# ads1115_2.net
KiCad netlist of a schematic drawn in EAGLE
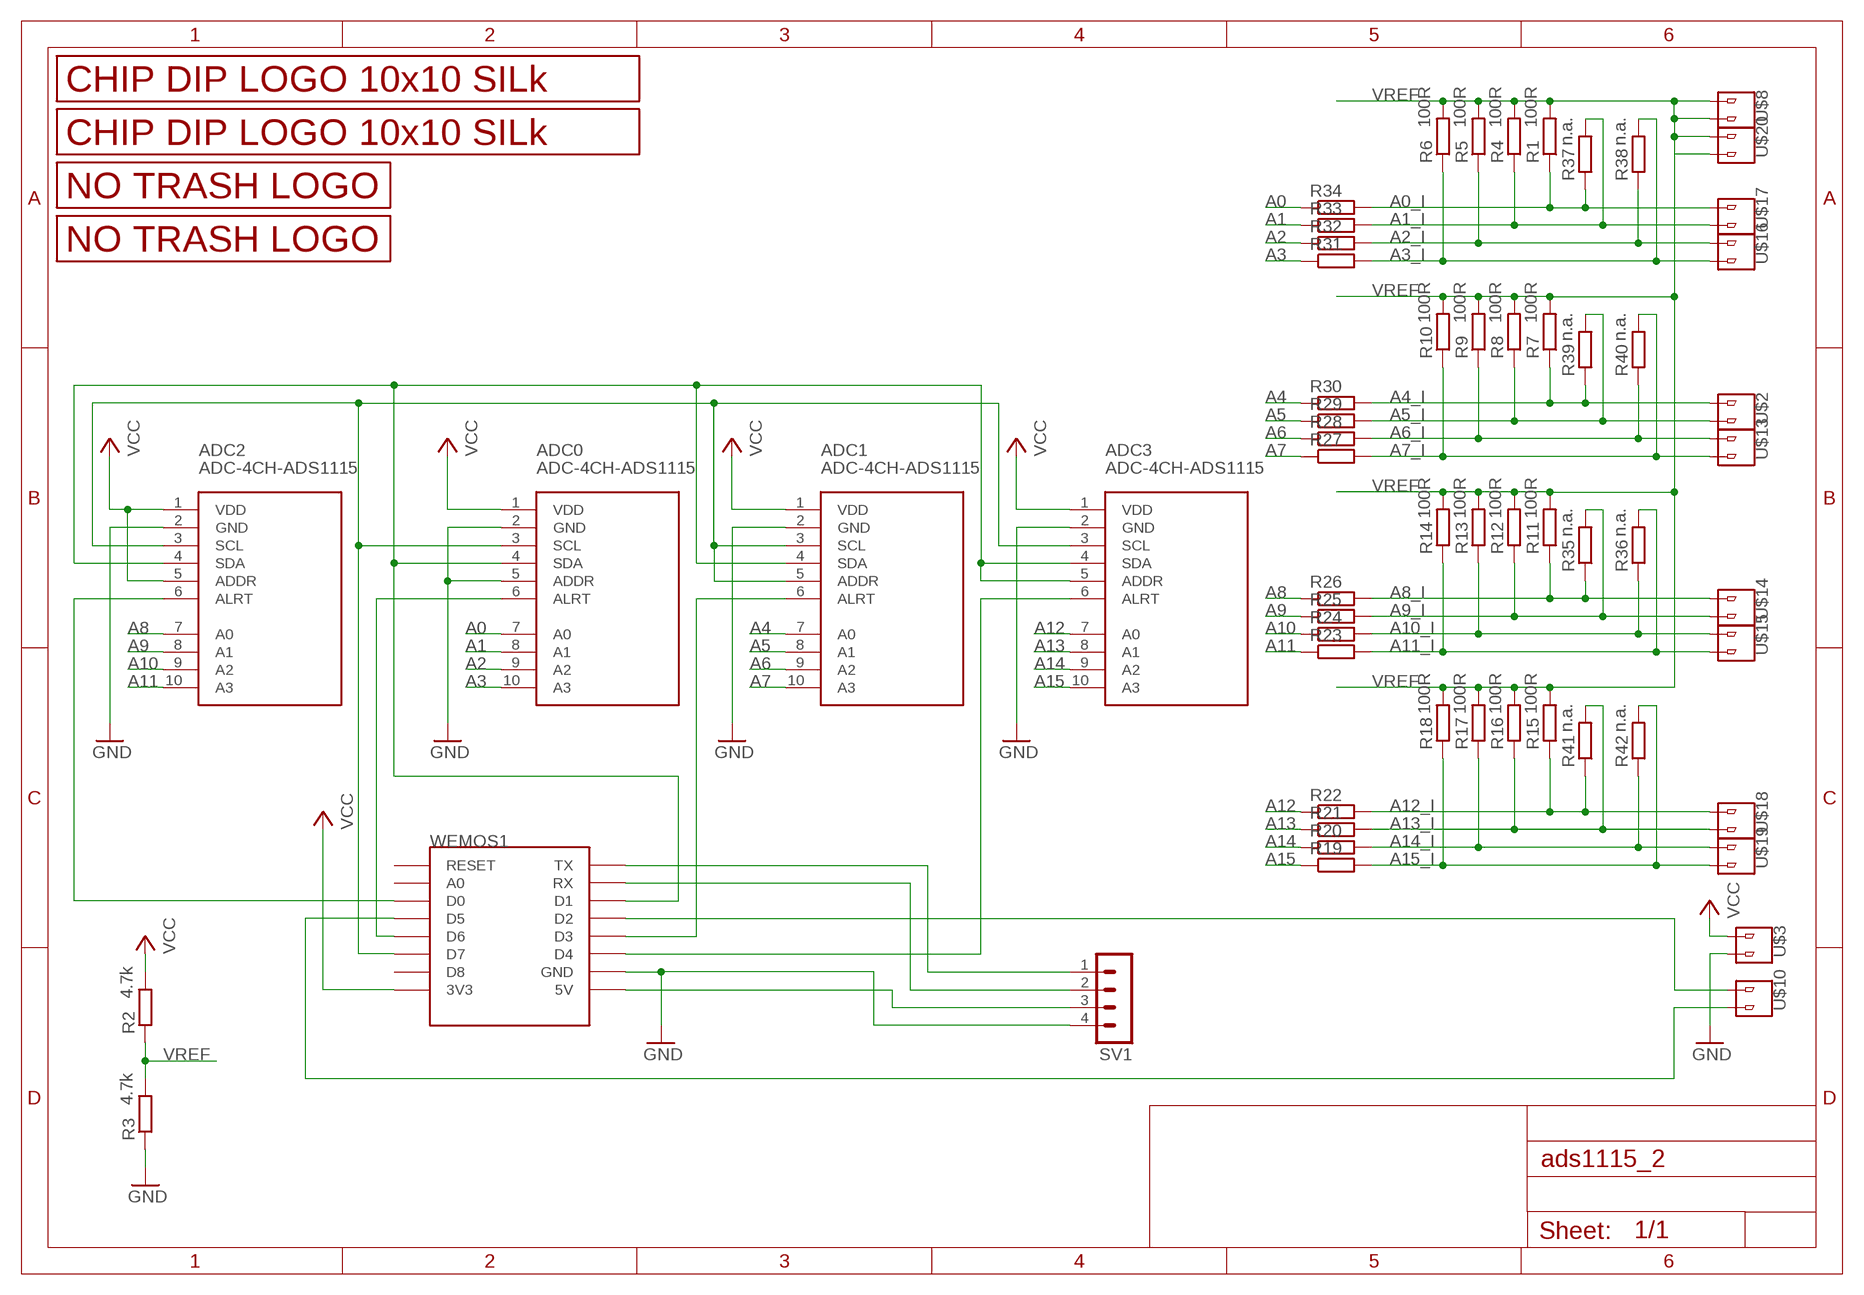
[diagram p0: schematic, sheet 1]

(export (version "E")
  (design (tool "Eeschema 10.0.6"))
  (components
    (comp (ref "ADC0")
      (value "ADC-4CH-ADS1115")
      (footprint "eagle-import:ADC-4CH-ADS1115_NO")
      (libsource (lib "eagle-import") (part "ADC-4CH-ADS1115"))
    )
    (comp (ref "ADC1")
      (value "ADC-4CH-ADS1115")
      (footprint "eagle-import:ADC-4CH-ADS1115_NO")
      (libsource (lib "eagle-import") (part "ADC-4CH-ADS1115"))
    )
    (comp (ref "ADC2")
      (value "ADC-4CH-ADS1115")
      (footprint "eagle-import:ADC-4CH-ADS1115_NO")
      (libsource (lib "eagle-import") (part "ADC-4CH-ADS1115"))
    )
    (comp (ref "ADC3")
      (value "ADC-4CH-ADS1115")
      (footprint "eagle-import:ADC-4CH-ADS1115_NO")
      (libsource (lib "eagle-import") (part "ADC-4CH-ADS1115"))
    )
    (comp (ref "R1")
      (value "100R")
      (footprint "eagle-import:M0805")
      (libsource (lib "eagle-import") (part "R-EU_M0805"))
    )
    (comp (ref "R2")
      (value "4.7k")
      (footprint "eagle-import:M0805")
      (libsource (lib "eagle-import") (part "R-EU_M0805"))
    )
    (comp (ref "R3")
      (value "4.7k")
      (footprint "eagle-import:M0805")
      (libsource (lib "eagle-import") (part "R-EU_M0805"))
    )
    (comp (ref "R4")
      (value "100R")
      (footprint "eagle-import:M0805")
      (libsource (lib "eagle-import") (part "R-EU_M0805"))
    )
    (comp (ref "R5")
      (value "100R")
      (footprint "eagle-import:M0805")
      (libsource (lib "eagle-import") (part "R-EU_M0805"))
    )
    (comp (ref "R6")
      (value "100R")
      (footprint "eagle-import:M0805")
      (libsource (lib "eagle-import") (part "R-EU_M0805"))
    )
    (comp (ref "R7")
      (value "100R")
      (footprint "eagle-import:M0805")
      (libsource (lib "eagle-import") (part "R-EU_M0805"))
    )
    (comp (ref "R8")
      (value "100R")
      (footprint "eagle-import:M0805")
      (libsource (lib "eagle-import") (part "R-EU_M0805"))
    )
    (comp (ref "R9")
      (value "100R")
      (footprint "eagle-import:M0805")
      (libsource (lib "eagle-import") (part "R-EU_M0805"))
    )
    (comp (ref "R10")
      (value "100R")
      (footprint "eagle-import:M0805")
      (libsource (lib "eagle-import") (part "R-EU_M0805"))
    )
    (comp (ref "R11")
      (value "100R")
      (footprint "eagle-import:M0805")
      (libsource (lib "eagle-import") (part "R-EU_M0805"))
    )
    (comp (ref "R12")
      (value "100R")
      (footprint "eagle-import:M0805")
      (libsource (lib "eagle-import") (part "R-EU_M0805"))
    )
    (comp (ref "R13")
      (value "100R")
      (footprint "eagle-import:M0805")
      (libsource (lib "eagle-import") (part "R-EU_M0805"))
    )
    (comp (ref "R14")
      (value "100R")
      (footprint "eagle-import:M0805")
      (libsource (lib "eagle-import") (part "R-EU_M0805"))
    )
    (comp (ref "R15")
      (value "100R")
      (footprint "eagle-import:M0805")
      (libsource (lib "eagle-import") (part "R-EU_M0805"))
    )
    (comp (ref "R16")
      (value "100R")
      (footprint "eagle-import:M0805")
      (libsource (lib "eagle-import") (part "R-EU_M0805"))
    )
    (comp (ref "R17")
      (value "100R")
      (footprint "eagle-import:M0805")
      (libsource (lib "eagle-import") (part "R-EU_M0805"))
    )
    (comp (ref "R18")
      (value "100R")
      (footprint "eagle-import:M0805")
      (libsource (lib "eagle-import") (part "R-EU_M0805"))
    )
    (comp (ref "R19")
      (value "1k")
      (footprint "eagle-import:M0805")
      (libsource (lib "eagle-import") (part "R-EU_M0805"))
    )
    (comp (ref "R20")
      (value "1k")
      (footprint "eagle-import:M0805")
      (libsource (lib "eagle-import") (part "R-EU_M0805"))
    )
    (comp (ref "R21")
      (value "1k")
      (footprint "eagle-import:M0805")
      (libsource (lib "eagle-import") (part "R-EU_M0805"))
    )
    (comp (ref "R22")
      (value "1k")
      (footprint "eagle-import:M0805")
      (libsource (lib "eagle-import") (part "R-EU_M0805"))
    )
    (comp (ref "R23")
      (value "1k")
      (footprint "eagle-import:M0805")
      (libsource (lib "eagle-import") (part "R-EU_M0805"))
    )
    (comp (ref "R24")
      (value "1k")
      (footprint "eagle-import:M0805")
      (libsource (lib "eagle-import") (part "R-EU_M0805"))
    )
    (comp (ref "R25")
      (value "1k")
      (footprint "eagle-import:M0805")
      (libsource (lib "eagle-import") (part "R-EU_M0805"))
    )
    (comp (ref "R26")
      (value "1k")
      (footprint "eagle-import:M0805")
      (libsource (lib "eagle-import") (part "R-EU_M0805"))
    )
    (comp (ref "R27")
      (value "1k")
      (footprint "eagle-import:M0805")
      (libsource (lib "eagle-import") (part "R-EU_M0805"))
    )
    (comp (ref "R28")
      (value "1k")
      (footprint "eagle-import:M0805")
      (libsource (lib "eagle-import") (part "R-EU_M0805"))
    )
    (comp (ref "R29")
      (value "1k")
      (footprint "eagle-import:M0805")
      (libsource (lib "eagle-import") (part "R-EU_M0805"))
    )
    (comp (ref "R30")
      (value "1k")
      (footprint "eagle-import:M0805")
      (libsource (lib "eagle-import") (part "R-EU_M0805"))
    )
    (comp (ref "R31")
      (value "1k")
      (footprint "eagle-import:M0805")
      (libsource (lib "eagle-import") (part "R-EU_M0805"))
    )
    (comp (ref "R32")
      (value "1k")
      (footprint "eagle-import:M0805")
      (libsource (lib "eagle-import") (part "R-EU_M0805"))
    )
    (comp (ref "R33")
      (value "1k")
      (footprint "eagle-import:M0805")
      (libsource (lib "eagle-import") (part "R-EU_M0805"))
    )
    (comp (ref "R34")
      (value "1k")
      (footprint "eagle-import:M0805")
      (libsource (lib "eagle-import") (part "R-EU_M0805"))
    )
    (comp (ref "R35")
      (value "n.a.")
      (footprint "eagle-import:M0805")
      (libsource (lib "eagle-import") (part "R-EU_M0805"))
    )
    (comp (ref "R36")
      (value "n.a.")
      (footprint "eagle-import:M0805")
      (libsource (lib "eagle-import") (part "R-EU_M0805"))
    )
    (comp (ref "R37")
      (value "n.a.")
      (footprint "eagle-import:M0805")
      (libsource (lib "eagle-import") (part "R-EU_M0805"))
    )
    (comp (ref "R38")
      (value "n.a.")
      (footprint "eagle-import:M0805")
      (libsource (lib "eagle-import") (part "R-EU_M0805"))
    )
    (comp (ref "R39")
      (value "n.a.")
      (footprint "eagle-import:M0805")
      (libsource (lib "eagle-import") (part "R-EU_M0805"))
    )
    (comp (ref "R40")
      (value "n.a.")
      (footprint "eagle-import:M0805")
      (libsource (lib "eagle-import") (part "R-EU_M0805"))
    )
    (comp (ref "R41")
      (value "n.a.")
      (footprint "eagle-import:M0805")
      (libsource (lib "eagle-import") (part "R-EU_M0805"))
    )
    (comp (ref "R42")
      (value "n.a.")
      (footprint "eagle-import:M0805")
      (libsource (lib "eagle-import") (part "R-EU_M0805"))
    )
    (comp (ref "SV1")
      (value "MA04-1")
      (footprint "eagle-import:MA04-1")
      (libsource (lib "eagle-import") (part "MA04-1"))
    )
    (comp (ref "U$1")
      (value "LOGO_10X10_SILK")
      (footprint "eagle-import:LOGO2_10X10_SILK")
      (libsource (lib "eagle-import") (part "LOGO_10X10_SILK"))
    )
    (comp (ref "U$2")
      (value "V1")
      (footprint "eagle-import:2_SCREW_PIN")
      (libsource (lib "eagle-import") (part "2_PIN_CONNECTOR"))
    )
    (comp (ref "U$3")
      (value "V1")
      (footprint "eagle-import:2_SCREW_PIN")
      (libsource (lib "eagle-import") (part "2_PIN_CONNECTOR"))
    )
    (comp (ref "U$4")
      (value "LOGO_NO_TRASHNO_TRASH")
      (footprint "eagle-import:LOGO_ROHS_NO_TRASH")
      (libsource (lib "eagle-import") (part "LOGO_NO_TRASHNO_TRASH"))
    )
    (comp (ref "U$8")
      (value "V1")
      (footprint "eagle-import:2_SCREW_PIN")
      (libsource (lib "eagle-import") (part "2_PIN_CONNECTOR"))
    )
    (comp (ref "U$9")
      (value "LOGO_NO_TRASHROHS")
      (footprint "eagle-import:LOGO_ROHS_SYM")
      (libsource (lib "eagle-import") (part "LOGO_NO_TRASHROHS"))
    )
    (comp (ref "U$10")
      (value "V1")
      (footprint "eagle-import:2_SCREW_PIN")
      (libsource (lib "eagle-import") (part "2_PIN_CONNECTOR"))
    )
    (comp (ref "U$11")
      (value "LOGO_10X10_SILK")
      (footprint "eagle-import:LOGO2_10X10_SILK")
      (libsource (lib "eagle-import") (part "LOGO_10X10_SILK"))
    )
    (comp (ref "U$13")
      (value "V1")
      (footprint "eagle-import:2_SCREW_PIN")
      (libsource (lib "eagle-import") (part "2_PIN_CONNECTOR"))
    )
    (comp (ref "U$14")
      (value "V1")
      (footprint "eagle-import:2_SCREW_PIN")
      (libsource (lib "eagle-import") (part "2_PIN_CONNECTOR"))
    )
    (comp (ref "U$15")
      (value "V1")
      (footprint "eagle-import:2_SCREW_PIN")
      (libsource (lib "eagle-import") (part "2_PIN_CONNECTOR"))
    )
    (comp (ref "U$16")
      (value "V1")
      (footprint "eagle-import:2_SCREW_PIN")
      (libsource (lib "eagle-import") (part "2_PIN_CONNECTOR"))
    )
    (comp (ref "U$17")
      (value "V1")
      (footprint "eagle-import:2_SCREW_PIN")
      (libsource (lib "eagle-import") (part "2_PIN_CONNECTOR"))
    )
    (comp (ref "U$18")
      (value "V1")
      (footprint "eagle-import:2_SCREW_PIN")
      (libsource (lib "eagle-import") (part "2_PIN_CONNECTOR"))
    )
    (comp (ref "U$19")
      (value "V1")
      (footprint "eagle-import:2_SCREW_PIN")
      (libsource (lib "eagle-import") (part "2_PIN_CONNECTOR"))
    )
    (comp (ref "U$20")
      (value "V1")
      (footprint "eagle-import:2_SCREW_PIN")
      (libsource (lib "eagle-import") (part "2_PIN_CONNECTOR"))
    )
    (comp (ref "WEMOS1")
      (value "WEMOS-D1-MINITXT")
      (footprint "eagle-import:WEMOS-D1-MINI")
      (libsource (lib "eagle-import") (part "WEMOS-D1-MINITXT"))
    )
  )
  (nets
    (net (code "1") (name "/A0") (class "Default")
      (node (ref "ADC0") (pin "7") (pinfunction "A0_7") (pintype "input"))
      (node (ref "R34") (pin "1") (pinfunction "1_1") (pintype "passive"))
    )
    (net (code "2") (name "/A0_I") (class "Default")
      (node (ref "R1") (pin "1") (pinfunction "1_1") (pintype "passive"))
      (node (ref "R34") (pin "2") (pinfunction "2_2") (pintype "passive"))
      (node (ref "R37") (pin "1") (pinfunction "1_1") (pintype "passive"))
      (node (ref "U$17") (pin "P$1") (pinfunction "1_P$1") (pintype "passive"))
    )
    (net (code "3") (name "/A1") (class "Default")
      (node (ref "ADC0") (pin "8") (pinfunction "A1_8") (pintype "input"))
      (node (ref "R33") (pin "1") (pinfunction "1_1") (pintype "passive"))
    )
    (net (code "4") (name "/A1_I") (class "Default")
      (node (ref "R33") (pin "2") (pinfunction "2_2") (pintype "passive"))
      (node (ref "R37") (pin "2") (pinfunction "2_2") (pintype "passive"))
      (node (ref "R4") (pin "1") (pinfunction "1_1") (pintype "passive"))
      (node (ref "U$17") (pin "P$2") (pinfunction "2_P$2") (pintype "passive"))
    )
    (net (code "5") (name "/A2") (class "Default")
      (node (ref "ADC0") (pin "9") (pinfunction "A2_9") (pintype "input"))
      (node (ref "R32") (pin "1") (pinfunction "1_1") (pintype "passive"))
    )
    (net (code "6") (name "/A2_I") (class "Default")
      (node (ref "R32") (pin "2") (pinfunction "2_2") (pintype "passive"))
      (node (ref "R38") (pin "1") (pinfunction "1_1") (pintype "passive"))
      (node (ref "R5") (pin "1") (pinfunction "1_1") (pintype "passive"))
      (node (ref "U$16") (pin "P$1") (pinfunction "1_P$1") (pintype "passive"))
    )
    (net (code "7") (name "/A3") (class "Default")
      (node (ref "ADC0") (pin "10") (pinfunction "A3_10") (pintype "input"))
      (node (ref "R31") (pin "1") (pinfunction "1_1") (pintype "passive"))
    )
    (net (code "8") (name "/A3_I") (class "Default")
      (node (ref "R31") (pin "2") (pinfunction "2_2") (pintype "passive"))
      (node (ref "R38") (pin "2") (pinfunction "2_2") (pintype "passive"))
      (node (ref "R6") (pin "1") (pinfunction "1_1") (pintype "passive"))
      (node (ref "U$16") (pin "P$2") (pinfunction "2_P$2") (pintype "passive"))
    )
    (net (code "9") (name "/A4") (class "Default")
      (node (ref "ADC1") (pin "7") (pinfunction "A0_7") (pintype "input"))
      (node (ref "R30") (pin "1") (pinfunction "1_1") (pintype "passive"))
    )
    (net (code "10") (name "/A4_I") (class "Default")
      (node (ref "R30") (pin "2") (pinfunction "2_2") (pintype "passive"))
      (node (ref "R39") (pin "1") (pinfunction "1_1") (pintype "passive"))
      (node (ref "R7") (pin "1") (pinfunction "1_1") (pintype "passive"))
      (node (ref "U$2") (pin "P$1") (pinfunction "1_P$1") (pintype "passive"))
    )
    (net (code "11") (name "/A5") (class "Default")
      (node (ref "ADC1") (pin "8") (pinfunction "A1_8") (pintype "input"))
      (node (ref "R29") (pin "1") (pinfunction "1_1") (pintype "passive"))
    )
    (net (code "12") (name "/A5_I") (class "Default")
      (node (ref "R29") (pin "2") (pinfunction "2_2") (pintype "passive"))
      (node (ref "R39") (pin "2") (pinfunction "2_2") (pintype "passive"))
      (node (ref "R8") (pin "1") (pinfunction "1_1") (pintype "passive"))
      (node (ref "U$2") (pin "P$2") (pinfunction "2_P$2") (pintype "passive"))
    )
    (net (code "13") (name "/A6") (class "Default")
      (node (ref "ADC1") (pin "9") (pinfunction "A2_9") (pintype "input"))
      (node (ref "R28") (pin "1") (pinfunction "1_1") (pintype "passive"))
    )
    (net (code "14") (name "/A6_I") (class "Default")
      (node (ref "R28") (pin "2") (pinfunction "2_2") (pintype "passive"))
      (node (ref "R40") (pin "1") (pinfunction "1_1") (pintype "passive"))
      (node (ref "R9") (pin "1") (pinfunction "1_1") (pintype "passive"))
      (node (ref "U$13") (pin "P$1") (pinfunction "1_P$1") (pintype "passive"))
    )
    (net (code "15") (name "/A7") (class "Default")
      (node (ref "ADC1") (pin "10") (pinfunction "A3_10") (pintype "input"))
      (node (ref "R27") (pin "1") (pinfunction "1_1") (pintype "passive"))
    )
    (net (code "16") (name "/A7_I") (class "Default")
      (node (ref "R10") (pin "1") (pinfunction "1_1") (pintype "passive"))
      (node (ref "R27") (pin "2") (pinfunction "2_2") (pintype "passive"))
      (node (ref "R40") (pin "2") (pinfunction "2_2") (pintype "passive"))
      (node (ref "U$13") (pin "P$2") (pinfunction "2_P$2") (pintype "passive"))
    )
    (net (code "17") (name "/A8") (class "Default")
      (node (ref "ADC2") (pin "7") (pinfunction "A0_7") (pintype "input"))
      (node (ref "R26") (pin "1") (pinfunction "1_1") (pintype "passive"))
    )
    (net (code "18") (name "/A8_I") (class "Default")
      (node (ref "R11") (pin "1") (pinfunction "1_1") (pintype "passive"))
      (node (ref "R26") (pin "2") (pinfunction "2_2") (pintype "passive"))
      (node (ref "R35") (pin "1") (pinfunction "1_1") (pintype "passive"))
      (node (ref "U$14") (pin "P$1") (pinfunction "1_P$1") (pintype "passive"))
    )
    (net (code "19") (name "/A9") (class "Default")
      (node (ref "ADC2") (pin "8") (pinfunction "A1_8") (pintype "input"))
      (node (ref "R25") (pin "1") (pinfunction "1_1") (pintype "passive"))
    )
    (net (code "20") (name "/A9_I") (class "Default")
      (node (ref "R12") (pin "1") (pinfunction "1_1") (pintype "passive"))
      (node (ref "R25") (pin "2") (pinfunction "2_2") (pintype "passive"))
      (node (ref "R35") (pin "2") (pinfunction "2_2") (pintype "passive"))
      (node (ref "U$14") (pin "P$2") (pinfunction "2_P$2") (pintype "passive"))
    )
    (net (code "21") (name "/A10") (class "Default")
      (node (ref "ADC2") (pin "9") (pinfunction "A2_9") (pintype "input"))
      (node (ref "R24") (pin "1") (pinfunction "1_1") (pintype "passive"))
    )
    (net (code "22") (name "/A10_I") (class "Default")
      (node (ref "R13") (pin "1") (pinfunction "1_1") (pintype "passive"))
      (node (ref "R24") (pin "2") (pinfunction "2_2") (pintype "passive"))
      (node (ref "R36") (pin "1") (pinfunction "1_1") (pintype "passive"))
      (node (ref "U$15") (pin "P$1") (pinfunction "1_P$1") (pintype "passive"))
    )
    (net (code "23") (name "/A11") (class "Default")
      (node (ref "ADC2") (pin "10") (pinfunction "A3_10") (pintype "input"))
      (node (ref "R23") (pin "1") (pinfunction "1_1") (pintype "passive"))
    )
    (net (code "24") (name "/A11_I") (class "Default")
      (node (ref "R14") (pin "1") (pinfunction "1_1") (pintype "passive"))
      (node (ref "R23") (pin "2") (pinfunction "2_2") (pintype "passive"))
      (node (ref "R36") (pin "2") (pinfunction "2_2") (pintype "passive"))
      (node (ref "U$15") (pin "P$2") (pinfunction "2_P$2") (pintype "passive"))
    )
    (net (code "25") (name "/A12") (class "Default")
      (node (ref "ADC3") (pin "7") (pinfunction "A0_7") (pintype "input"))
      (node (ref "R22") (pin "1") (pinfunction "1_1") (pintype "passive"))
    )
    (net (code "26") (name "/A12_I") (class "Default")
      (node (ref "R15") (pin "1") (pinfunction "1_1") (pintype "passive"))
      (node (ref "R22") (pin "2") (pinfunction "2_2") (pintype "passive"))
      (node (ref "R41") (pin "1") (pinfunction "1_1") (pintype "passive"))
      (node (ref "U$18") (pin "P$1") (pinfunction "1_P$1") (pintype "passive"))
    )
    (net (code "27") (name "/A13") (class "Default")
      (node (ref "ADC3") (pin "8") (pinfunction "A1_8") (pintype "input"))
      (node (ref "R21") (pin "1") (pinfunction "1_1") (pintype "passive"))
    )
    (net (code "28") (name "/A13_I") (class "Default")
      (node (ref "R16") (pin "1") (pinfunction "1_1") (pintype "passive"))
      (node (ref "R21") (pin "2") (pinfunction "2_2") (pintype "passive"))
      (node (ref "R41") (pin "2") (pinfunction "2_2") (pintype "passive"))
      (node (ref "U$18") (pin "P$2") (pinfunction "2_P$2") (pintype "passive"))
    )
    (net (code "29") (name "/A14") (class "Default")
      (node (ref "ADC3") (pin "9") (pinfunction "A2_9") (pintype "input"))
      (node (ref "R20") (pin "1") (pinfunction "1_1") (pintype "passive"))
    )
    (net (code "30") (name "/A14_I") (class "Default")
      (node (ref "R17") (pin "1") (pinfunction "1_1") (pintype "passive"))
      (node (ref "R20") (pin "2") (pinfunction "2_2") (pintype "passive"))
      (node (ref "R42") (pin "1") (pinfunction "1_1") (pintype "passive"))
      (node (ref "U$19") (pin "P$1") (pinfunction "1_P$1") (pintype "passive"))
    )
    (net (code "31") (name "/A15") (class "Default")
      (node (ref "ADC3") (pin "10") (pinfunction "A3_10") (pintype "input"))
      (node (ref "R19") (pin "1") (pinfunction "1_1") (pintype "passive"))
    )
    (net (code "32") (name "/A15_I") (class "Default")
      (node (ref "R18") (pin "1") (pinfunction "1_1") (pintype "passive"))
      (node (ref "R19") (pin "2") (pinfunction "2_2") (pintype "passive"))
      (node (ref "R42") (pin "2") (pinfunction "2_2") (pintype "passive"))
      (node (ref "U$19") (pin "P$2") (pinfunction "2_P$2") (pintype "passive"))
    )
    (net (code "33") (name "/VREF") (class "Default")
      (node (ref "R1") (pin "2") (pinfunction "2_2") (pintype "passive"))
      (node (ref "R10") (pin "2") (pinfunction "2_2") (pintype "passive"))
      (node (ref "R11") (pin "2") (pinfunction "2_2") (pintype "passive"))
      (node (ref "R12") (pin "2") (pinfunction "2_2") (pintype "passive"))
      (node (ref "R13") (pin "2") (pinfunction "2_2") (pintype "passive"))
      (node (ref "R14") (pin "2") (pinfunction "2_2") (pintype "passive"))
      (node (ref "R15") (pin "2") (pinfunction "2_2") (pintype "passive"))
      (node (ref "R16") (pin "2") (pinfunction "2_2") (pintype "passive"))
      (node (ref "R17") (pin "2") (pinfunction "2_2") (pintype "passive"))
      (node (ref "R18") (pin "2") (pinfunction "2_2") (pintype "passive"))
      (node (ref "R2") (pin "1") (pinfunction "1_1") (pintype "passive"))
      (node (ref "R3") (pin "2") (pinfunction "2_2") (pintype "passive"))
      (node (ref "R4") (pin "2") (pinfunction "2_2") (pintype "passive"))
      (node (ref "R5") (pin "2") (pinfunction "2_2") (pintype "passive"))
      (node (ref "R6") (pin "2") (pinfunction "2_2") (pintype "passive"))
      (node (ref "R7") (pin "2") (pinfunction "2_2") (pintype "passive"))
      (node (ref "R8") (pin "2") (pinfunction "2_2") (pintype "passive"))
      (node (ref "R9") (pin "2") (pinfunction "2_2") (pintype "passive"))
      (node (ref "U$20") (pin "P$1") (pinfunction "1_P$1") (pintype "passive"))
      (node (ref "U$20") (pin "P$2") (pinfunction "2_P$2") (pintype "passive"))
      (node (ref "U$8") (pin "P$1") (pinfunction "1_P$1") (pintype "passive"))
      (node (ref "U$8") (pin "P$2") (pinfunction "2_P$2") (pintype "passive"))
    )
    (net (code "34") (name "GND") (class "Default")
      (node (ref "ADC0") (pin "2") (pinfunction "GND_2") (pintype "power_in"))
      (node (ref "ADC0") (pin "5") (pinfunction "ADDR_5") (pintype "bidirectional"))
      (node (ref "ADC1") (pin "2") (pinfunction "GND_2") (pintype "power_in"))
      (node (ref "ADC2") (pin "2") (pinfunction "GND_2") (pintype "power_in"))
      (node (ref "ADC3") (pin "2") (pinfunction "GND_2") (pintype "power_in"))
      (node (ref "R3") (pin "1") (pinfunction "1_1") (pintype "passive"))
      (node (ref "SV1") (pin "4") (pinfunction "4_4") (pintype "passive"))
      (node (ref "U$3") (pin "P$2") (pinfunction "2_P$2") (pintype "passive"))
      (node (ref "WEMOS1") (pin "GND") (pinfunction "GND_GND") (pintype "bidirectional"))
    )
    (net (code "35") (name "Net-(ADC0-ALRT)") (class "Default")
      (node (ref "ADC0") (pin "6") (pinfunction "ALRT_6") (pintype "bidirectional"))
      (node (ref "WEMOS1") (pin "D6") (pinfunction "D6_D6") (pintype "bidirectional"))
    )
    (net (code "36") (name "Net-(ADC0-SCL)") (class "Default")
      (node (ref "ADC0") (pin "3") (pinfunction "SCL_3") (pintype "bidirectional"))
      (node (ref "ADC1") (pin "3") (pinfunction "SCL_3") (pintype "bidirectional"))
      (node (ref "ADC1") (pin "5") (pinfunction "ADDR_5") (pintype "bidirectional"))
      (node (ref "ADC2") (pin "3") (pinfunction "SCL_3") (pintype "bidirectional"))
      (node (ref "ADC3") (pin "3") (pinfunction "SCL_3") (pintype "bidirectional"))
      (node (ref "WEMOS1") (pin "D7") (pinfunction "D7_D7") (pintype "bidirectional"))
    )
    (net (code "37") (name "Net-(ADC0-SDA)") (class "Default")
      (node (ref "ADC0") (pin "4") (pinfunction "SDA_4") (pintype "bidirectional"))
      (node (ref "ADC1") (pin "4") (pinfunction "SDA_4") (pintype "bidirectional"))
      (node (ref "ADC2") (pin "4") (pinfunction "SDA_4") (pintype "bidirectional"))
      (node (ref "ADC3") (pin "4") (pinfunction "SDA_4") (pintype "bidirectional"))
      (node (ref "ADC3") (pin "5") (pinfunction "ADDR_5") (pintype "bidirectional"))
      (node (ref "WEMOS1") (pin "D1") (pinfunction "D1_D1") (pintype "bidirectional"))
    )
    (net (code "38") (name "Net-(ADC1-ALRT)") (class "Default")
      (node (ref "ADC1") (pin "6") (pinfunction "ALRT_6") (pintype "bidirectional"))
      (node (ref "WEMOS1") (pin "D3") (pinfunction "D3_D3") (pintype "bidirectional"))
    )
    (net (code "39") (name "Net-(ADC2-ALRT)") (class "Default")
      (node (ref "ADC2") (pin "6") (pinfunction "ALRT_6") (pintype "bidirectional"))
      (node (ref "WEMOS1") (pin "D0") (pinfunction "D0_D0") (pintype "bidirectional"))
    )
    (net (code "40") (name "Net-(ADC3-ALRT)") (class "Default")
      (node (ref "ADC3") (pin "6") (pinfunction "ALRT_6") (pintype "bidirectional"))
      (node (ref "WEMOS1") (pin "D4") (pinfunction "D4_D4") (pintype "bidirectional"))
    )
    (net (code "41") (name "Net-(SV1-Pad1)") (class "Default")
      (node (ref "SV1") (pin "1") (pinfunction "1_1") (pintype "passive"))
      (node (ref "WEMOS1") (pin "TX") (pinfunction "TX_TX") (pintype "bidirectional"))
    )
    (net (code "42") (name "Net-(SV1-Pad2)") (class "Default")
      (node (ref "SV1") (pin "2") (pinfunction "2_2") (pintype "passive"))
      (node (ref "WEMOS1") (pin "RX") (pinfunction "RX_RX") (pintype "bidirectional"))
    )
    (net (code "43") (name "Net-(SV1-Pad3)") (class "Default")
      (node (ref "SV1") (pin "3") (pinfunction "3_3") (pintype "passive"))
      (node (ref "WEMOS1") (pin "5V") (pinfunction "5V_5V") (pintype "bidirectional"))
    )
    (net (code "44") (name "Net-(U$10-1)") (class "Default")
      (node (ref "U$10") (pin "P$1") (pinfunction "1_P$1") (pintype "passive"))
      (node (ref "WEMOS1") (pin "D2") (pinfunction "D2_D2") (pintype "bidirectional"))
    )
    (net (code "45") (name "Net-(U$10-2)") (class "Default")
      (node (ref "U$10") (pin "P$2") (pinfunction "2_P$2") (pintype "passive"))
      (node (ref "WEMOS1") (pin "D5") (pinfunction "D5_D5") (pintype "bidirectional"))
    )
    (net (code "46") (name "VCC") (class "Default")
      (node (ref "ADC0") (pin "1") (pinfunction "VDD_1") (pintype "power_in"))
      (node (ref "ADC1") (pin "1") (pinfunction "VDD_1") (pintype "power_in"))
      (node (ref "ADC2") (pin "1") (pinfunction "VDD_1") (pintype "power_in"))
      (node (ref "ADC2") (pin "5") (pinfunction "ADDR_5") (pintype "bidirectional"))
      (node (ref "ADC3") (pin "1") (pinfunction "VDD_1") (pintype "power_in"))
      (node (ref "R2") (pin "2") (pinfunction "2_2") (pintype "passive"))
      (node (ref "U$3") (pin "P$1") (pinfunction "1_P$1") (pintype "passive"))
      (node (ref "WEMOS1") (pin "3V3") (pinfunction "3V3_3V3") (pintype "bidirectional"))
    )
    (net (code "47") (name "unconnected-(WEMOS1-PadA0)") (class "Default")
      (node (ref "WEMOS1") (pin "A0") (pinfunction "A0_A0") (pintype "bidirectional"))
    )
    (net (code "48") (name "unconnected-(WEMOS1-PadD8)") (class "Default")
      (node (ref "WEMOS1") (pin "D8") (pinfunction "D8_D8") (pintype "bidirectional"))
    )
    (net (code "49") (name "unconnected-(WEMOS1-PadRESET)") (class "Default")
      (node (ref "WEMOS1") (pin "RESET") (pinfunction "RESET_RESET") (pintype "bidirectional"))
    )
  )
)
